# Payload_ESP.net
KiCad netlist of a schematic drawn in Altium Designer
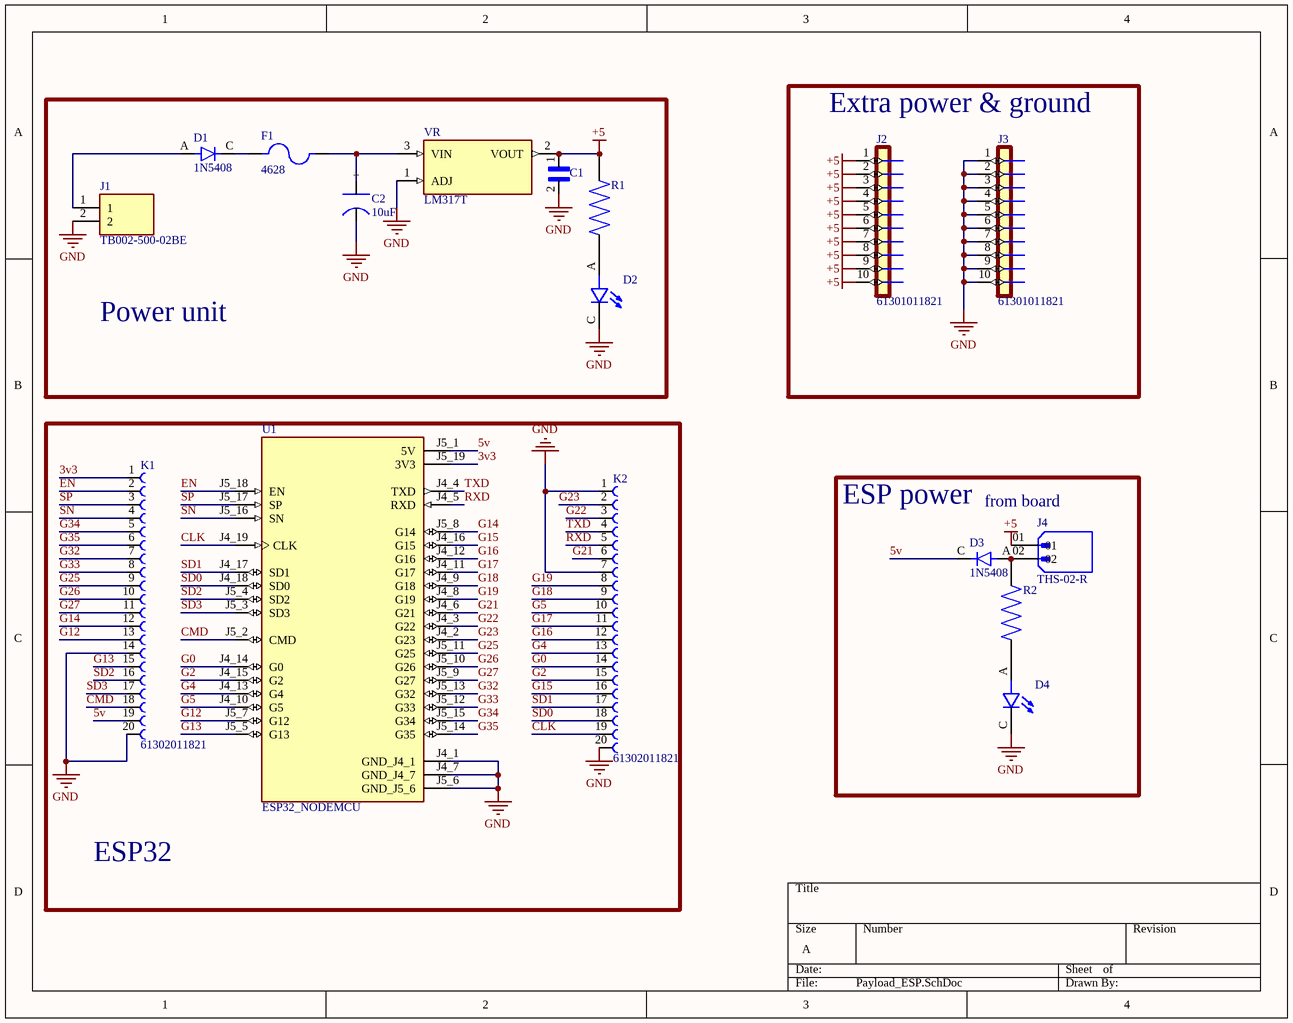
[diagram p0: Payload_ESP.SchDoc]

(export (version "E")
  (design (tool "Eeschema 10.0.6"))
  (components
    (comp (ref "C1")
      (value "FA14X8R1H104KNU06")
      (footprint "CAPRB250W50L450T300H550")
      (description "0.1 ÂµF Â±10% 50V Ceramic Capacitor X8R Radial")
      (fields (field (name "MF") "TDK"))
      (libsource (lib "Martius") (part "FA14X8R1H104KNU06"))
    )
    (comp (ref "C2")
      (value "10uF")
      (footprint "860020672010")
      (libsource (lib "S.M.R") (part "860020672010"))
    )
    (comp (ref "D1")
      (value "1N5408")
      (footprint "DIOAD2006W127L950D530")
      (description "Diode Standard 1000V 3A Through Hole DO-201AD")
      (fields (field (name "MF") "ON"))
      (libsource (lib "Martius") (part "1N5408"))
    )
    (comp (ref "D2")
      (value "151054RS03000")
      (footprint "LED_151054RS03000")
      (description "Red 623nm LED Indication - Discrete 1.9V Radial")
      (fields (field (name "MF") "Wurth Elektronik"))
      (libsource (lib "Martius") (part "151054RS03000"))
    )
    (comp (ref "D3")
      (value "1N5408")
      (footprint "DIOAD2006W127L950D530")
      (description "Diode Standard 1000V 3A Through Hole DO-201AD")
      (fields (field (name "MF") "ON"))
      (libsource (lib "Martius") (part "1N5408"))
    )
    (comp (ref "D4")
      (value "151054RS03000")
      (footprint "LED_151054RS03000")
      (description "Red 623nm LED Indication - Discrete 1.9V Radial")
      (fields (field (name "MF") "Wurth Elektronik"))
      (libsource (lib "Martius") (part "151054RS03000"))
    )
    (comp (ref "F1")
      (value "4628")
      (footprint "FUSE_4628")
      (description "5mm Slim Line Fuse holder")
      (fields (field (name "MF") "Keystone"))
      (libsource (lib "Martius") (part "4628"))
    )
    (comp (ref "J1")
      (value "TB002-500-02BE")
      (footprint "CUI_TB002-500-02BE")
      (description "2~24 Poles, Screw Type, Horizontal, 5.0 Pitch, 22~12 (AWG), Terminal Block Connector")
      (fields (field (name "MF") "CUI Devices"))
      (libsource (lib "Martius") (part "TB002-500-02BE"))
    )
    (comp (ref "J2")
      (value "61301011821")
      (footprint "1X10-PIN")
      (description "10 Position Header Connector 0.100 (2.54mm) Through Hole Gold")
      (fields (field (name "MF") "Wurth Electronics"))
      (libsource (lib "Martius") (part "61301011821"))
    )
    (comp (ref "J3")
      (value "61301011821")
      (footprint "1X10-PIN")
      (description "10 Position Header Connector 0.100 (2.54mm) Through Hole Gold")
      (fields (field (name "MF") "Wurth Electronics"))
      (libsource (lib "Martius") (part "61301011821"))
    )
    (comp (ref "J4")
      (value "THS-02-R")
      (footprint "VALCON_THS-02-R")
      (libsource (lib "Martius") (part "THS-02-R"))
    )
    (comp (ref "K1")
      (value "61302011821")
      (footprint "61302011821")
      (description "20 Position Receptacle Connector 0.100 (2.54mm) Through Hole Gold")
      (fields (field (name "MF") "WÃ¼rth Elektronik"))
      (libsource (lib "Martius") (part "61302011821"))
    )
    (comp (ref "K2")
      (value "61302011821")
      (footprint "61302011821")
      (description "20 Position Receptacle Connector 0.100 (2.54mm) Through Hole Gold")
      (fields (field (name "MF") "WÃ¼rth Elektronik"))
      (libsource (lib "Martius") (part "61302011821"))
    )
    (comp (ref "R1")
      (value "MFR-25FBF52-1K")
      (footprint "RESAD1100W55L680D260")
      (description "1.07 kOhms Â±1% 0.25W, 1/4W Through Hole Resistor Axial - Metal Film")
      (fields (field (name "MF") "Yageo"))
      (libsource (lib "Martius") (part "MFR-25FBF52-1K"))
    )
    (comp (ref "R2")
      (value "MFR-25FBF52-1K")
      (footprint "RESAD1100W55L680D260")
      (description "1.07 kOhms Â±1% 0.25W, 1/4W Through Hole Resistor Axial - Metal Film")
      (fields (field (name "MF") "Yageo"))
      (libsource (lib "Martius") (part "MFR-25FBF52-1K"))
    )
    (comp (ref "U1")
      (value "ESP32_NODEMCU")
      (footprint "MODULE_ESP32_NODEMCU")
      (fields (field (name "MF") "Espressif Systems") (field (name "MP") "ESP32 NODEMCU"))
      (libsource (lib "Martius") (part "ESP32_NODEMCU"))
    )
    (comp (ref "VR")
      (value "LM317T")
      (footprint "TO254P1054X470X1955-3")
      (description "Linear Voltage Regulator IC 1 Output 1.5A TO-220-3")
      (fields (field (name "MF") "Texas Instruments"))
      (libsource (lib "Martius") (part "LM317T"))
    )
  )
  (nets
    (net (code "1") (name "+5") (class "Default")
      (node (ref "C1") (pin "1") (pinfunction "1_1") (pintype "passive"))
      (node (ref "J2") (pin "1") (pinfunction "1_1") (pintype "bidirectional"))
      (node (ref "J2") (pin "10") (pinfunction "10_10") (pintype "bidirectional"))
      (node (ref "J2") (pin "2") (pinfunction "2_2") (pintype "bidirectional"))
      (node (ref "J2") (pin "3") (pinfunction "3_3") (pintype "bidirectional"))
      (node (ref "J2") (pin "4") (pinfunction "4_4") (pintype "bidirectional"))
      (node (ref "J2") (pin "5") (pinfunction "5_5") (pintype "bidirectional"))
      (node (ref "J2") (pin "6") (pinfunction "6_6") (pintype "bidirectional"))
      (node (ref "J2") (pin "7") (pinfunction "7_7") (pintype "bidirectional"))
      (node (ref "J2") (pin "8") (pinfunction "8_8") (pintype "bidirectional"))
      (node (ref "J2") (pin "9") (pinfunction "9_9") (pintype "bidirectional"))
      (node (ref "J4") (pin "01") (pinfunction "01_01") (pintype "passive"))
      (node (ref "R1") (pin "2") (pinfunction "2_2") (pintype "passive"))
      (node (ref "VR") (pin "2") (pinfunction "VOUT_2") (pintype "output"))
    )
    (net (code "2") (name "/3v3") (class "Default")
      (node (ref "K1") (pin "1") (pinfunction "1_1") (pintype "passive"))
      (node (ref "U1") (pin "J5_19") (pinfunction "3V3_J5_19") (pintype "power_in"))
    )
    (net (code "3") (name "/5v") (class "Default")
      (node (ref "D3") (pin "C") (pinfunction "C_C") (pintype "passive"))
      (node (ref "K1") (pin "19") (pinfunction "19_19") (pintype "passive"))
      (node (ref "U1") (pin "J5_1") (pinfunction "5V_J5_1") (pintype "power_in"))
    )
    (net (code "5") (name "/CLK") (class "Default")
      (node (ref "K2") (pin "19") (pinfunction "19_19") (pintype "passive"))
      (node (ref "U1") (pin "J4_19") (pinfunction "CLK_J4_19") (pintype "input"))
    )
    (net (code "6") (name "/CMD") (class "Default")
      (node (ref "K1") (pin "18") (pinfunction "18_18") (pintype "passive"))
      (node (ref "U1") (pin "J5_2") (pinfunction "CMD_J5_2") (pintype "bidirectional"))
    )
    (net (code "7") (name "/EN") (class "Default")
      (node (ref "K1") (pin "2") (pinfunction "2_2") (pintype "passive"))
      (node (ref "U1") (pin "J5_18") (pinfunction "EN_J5_18") (pintype "input"))
    )
    (net (code "8") (name "/G0") (class "Default")
      (node (ref "K2") (pin "14") (pinfunction "14_14") (pintype "passive"))
      (node (ref "U1") (pin "J4_14") (pinfunction "G0_J4_14") (pintype "bidirectional"))
    )
    (net (code "9") (name "/G2") (class "Default")
      (node (ref "K2") (pin "15") (pinfunction "15_15") (pintype "passive"))
      (node (ref "U1") (pin "J4_15") (pinfunction "G2_J4_15") (pintype "bidirectional"))
    )
    (net (code "10") (name "/G4") (class "Default")
      (node (ref "K2") (pin "13") (pinfunction "13_13") (pintype "passive"))
      (node (ref "U1") (pin "J4_13") (pinfunction "G4_J4_13") (pintype "bidirectional"))
    )
    (net (code "11") (name "/G5") (class "Default")
      (node (ref "K2") (pin "10") (pinfunction "10_10") (pintype "passive"))
      (node (ref "U1") (pin "J4_10") (pinfunction "G5_J4_10") (pintype "bidirectional"))
    )
    (net (code "12") (name "/G12") (class "Default")
      (node (ref "K1") (pin "13") (pinfunction "13_13") (pintype "passive"))
      (node (ref "U1") (pin "J5_7") (pinfunction "G12_J5_7") (pintype "bidirectional"))
    )
    (net (code "13") (name "/G13") (class "Default")
      (node (ref "K1") (pin "15") (pinfunction "15_15") (pintype "passive"))
      (node (ref "U1") (pin "J5_5") (pinfunction "G13_J5_5") (pintype "bidirectional"))
    )
    (net (code "14") (name "/G14") (class "Default")
      (node (ref "K1") (pin "12") (pinfunction "12_12") (pintype "passive"))
      (node (ref "U1") (pin "J5_8") (pinfunction "G14_J5_8") (pintype "bidirectional"))
    )
    (net (code "15") (name "/G15") (class "Default")
      (node (ref "K2") (pin "16") (pinfunction "16_16") (pintype "passive"))
      (node (ref "U1") (pin "J4_16") (pinfunction "G15_J4_16") (pintype "bidirectional"))
    )
    (net (code "16") (name "/G16") (class "Default")
      (node (ref "K2") (pin "12") (pinfunction "12_12") (pintype "passive"))
      (node (ref "U1") (pin "J4_12") (pinfunction "G16_J4_12") (pintype "bidirectional"))
    )
    (net (code "17") (name "/G17") (class "Default")
      (node (ref "K2") (pin "11") (pinfunction "11_11") (pintype "passive"))
      (node (ref "U1") (pin "J4_11") (pinfunction "G17_J4_11") (pintype "bidirectional"))
    )
    (net (code "18") (name "/G18") (class "Default")
      (node (ref "K2") (pin "9") (pinfunction "9_9") (pintype "passive"))
      (node (ref "U1") (pin "J4_9") (pinfunction "G18_J4_9") (pintype "bidirectional"))
    )
    (net (code "19") (name "/G19") (class "Default")
      (node (ref "K2") (pin "8") (pinfunction "8_8") (pintype "passive"))
      (node (ref "U1") (pin "J4_8") (pinfunction "G19_J4_8") (pintype "bidirectional"))
    )
    (net (code "20") (name "/G21") (class "Default")
      (node (ref "K2") (pin "6") (pinfunction "6_6") (pintype "passive"))
      (node (ref "U1") (pin "J4_6") (pinfunction "G21_J4_6") (pintype "bidirectional"))
    )
    (net (code "21") (name "/G22") (class "Default")
      (node (ref "K2") (pin "3") (pinfunction "3_3") (pintype "passive"))
      (node (ref "U1") (pin "J4_3") (pinfunction "G22_J4_3") (pintype "bidirectional"))
    )
    (net (code "22") (name "/G23") (class "Default")
      (node (ref "K2") (pin "2") (pinfunction "2_2") (pintype "passive"))
      (node (ref "U1") (pin "J4_2") (pinfunction "G23_J4_2") (pintype "bidirectional"))
    )
    (net (code "23") (name "/G25") (class "Default")
      (node (ref "K1") (pin "9") (pinfunction "9_9") (pintype "passive"))
      (node (ref "U1") (pin "J5_11") (pinfunction "G25_J5_11") (pintype "bidirectional"))
    )
    (net (code "24") (name "/G26") (class "Default")
      (node (ref "K1") (pin "10") (pinfunction "10_10") (pintype "passive"))
      (node (ref "U1") (pin "J5_10") (pinfunction "G26_J5_10") (pintype "bidirectional"))
    )
    (net (code "25") (name "/G27") (class "Default")
      (node (ref "K1") (pin "11") (pinfunction "11_11") (pintype "passive"))
      (node (ref "U1") (pin "J5_9") (pinfunction "G27_J5_9") (pintype "bidirectional"))
    )
    (net (code "26") (name "/G32") (class "Default")
      (node (ref "K1") (pin "7") (pinfunction "7_7") (pintype "passive"))
      (node (ref "U1") (pin "J5_13") (pinfunction "G32_J5_13") (pintype "bidirectional"))
    )
    (net (code "27") (name "/G33") (class "Default")
      (node (ref "K1") (pin "8") (pinfunction "8_8") (pintype "passive"))
      (node (ref "U1") (pin "J5_12") (pinfunction "G33_J5_12") (pintype "bidirectional"))
    )
    (net (code "28") (name "/G34") (class "Default")
      (node (ref "K1") (pin "5") (pinfunction "5_5") (pintype "passive"))
      (node (ref "U1") (pin "J5_15") (pinfunction "G34_J5_15") (pintype "bidirectional"))
    )
    (net (code "29") (name "/G35") (class "Default")
      (node (ref "K1") (pin "6") (pinfunction "6_6") (pintype "passive"))
      (node (ref "U1") (pin "J5_14") (pinfunction "G35_J5_14") (pintype "bidirectional"))
    )
    (net (code "30") (name "/RXD") (class "Default")
      (node (ref "K2") (pin "5") (pinfunction "5_5") (pintype "passive"))
      (node (ref "U1") (pin "J4_5") (pinfunction "RXD_J4_5") (pintype "input"))
    )
    (net (code "31") (name "/SD0") (class "Default")
      (node (ref "K2") (pin "18") (pinfunction "18_18") (pintype "passive"))
      (node (ref "U1") (pin "J4_18") (pinfunction "SD0_J4_18") (pintype "bidirectional"))
    )
    (net (code "32") (name "/SD1") (class "Default")
      (node (ref "K2") (pin "17") (pinfunction "17_17") (pintype "passive"))
      (node (ref "U1") (pin "J4_17") (pinfunction "SD1_J4_17") (pintype "bidirectional"))
    )
    (net (code "33") (name "/SD2") (class "Default")
      (node (ref "K1") (pin "16") (pinfunction "16_16") (pintype "passive"))
      (node (ref "U1") (pin "J5_4") (pinfunction "SD2_J5_4") (pintype "bidirectional"))
    )
    (net (code "34") (name "/SD3") (class "Default")
      (node (ref "K1") (pin "17") (pinfunction "17_17") (pintype "passive"))
      (node (ref "U1") (pin "J5_3") (pinfunction "SD3_J5_3") (pintype "bidirectional"))
    )
    (net (code "35") (name "/SN") (class "Default")
      (node (ref "K1") (pin "4") (pinfunction "4_4") (pintype "passive"))
      (node (ref "U1") (pin "J5_16") (pinfunction "SN_J5_16") (pintype "input"))
    )
    (net (code "36") (name "/SP") (class "Default")
      (node (ref "K1") (pin "3") (pinfunction "3_3") (pintype "passive"))
      (node (ref "U1") (pin "J5_17") (pinfunction "SP_J5_17") (pintype "input"))
    )
    (net (code "37") (name "/TXD") (class "Default")
      (node (ref "K2") (pin "4") (pinfunction "4_4") (pintype "passive"))
      (node (ref "U1") (pin "J4_4") (pinfunction "TXD_J4_4") (pintype "output"))
    )
    (net (code "38") (name "GND") (class "Default")
      (node (ref "C1") (pin "2") (pinfunction "2_2") (pintype "passive"))
      (node (ref "C2") (pin "2") (pinfunction "-_2") (pintype "passive"))
      (node (ref "D2") (pin "C") (pinfunction "C_C") (pintype "passive"))
      (node (ref "D4") (pin "C") (pinfunction "C_C") (pintype "passive"))
      (node (ref "J1") (pin "2") (pinfunction "2_2") (pintype "passive"))
      (node (ref "J3") (pin "1") (pinfunction "1_1") (pintype "bidirectional"))
      (node (ref "J3") (pin "10") (pinfunction "10_10") (pintype "bidirectional"))
      (node (ref "J3") (pin "2") (pinfunction "2_2") (pintype "bidirectional"))
      (node (ref "J3") (pin "3") (pinfunction "3_3") (pintype "bidirectional"))
      (node (ref "J3") (pin "4") (pinfunction "4_4") (pintype "bidirectional"))
      (node (ref "J3") (pin "5") (pinfunction "5_5") (pintype "bidirectional"))
      (node (ref "J3") (pin "6") (pinfunction "6_6") (pintype "bidirectional"))
      (node (ref "J3") (pin "7") (pinfunction "7_7") (pintype "bidirectional"))
      (node (ref "J3") (pin "8") (pinfunction "8_8") (pintype "bidirectional"))
      (node (ref "J3") (pin "9") (pinfunction "9_9") (pintype "bidirectional"))
      (node (ref "K1") (pin "14") (pinfunction "14_14") (pintype "passive"))
      (node (ref "K1") (pin "20") (pinfunction "20_20") (pintype "passive"))
      (node (ref "K2") (pin "1") (pinfunction "1_1") (pintype "passive"))
      (node (ref "K2") (pin "20") (pinfunction "20_20") (pintype "passive"))
      (node (ref "K2") (pin "7") (pinfunction "7_7") (pintype "passive"))
      (node (ref "U1") (pin "J4_1") (pinfunction "GND_J4_1_J4_1") (pintype "power_in"))
      (node (ref "U1") (pin "J4_7") (pinfunction "GND_J4_7_J4_7") (pintype "power_in"))
      (node (ref "U1") (pin "J5_6") (pinfunction "GND_J5_6_J5_6") (pintype "power_in"))
      (node (ref "VR") (pin "1") (pinfunction "ADJ_1") (pintype "input"))
    )
    (net (code "39") (name "Net-(C2-+)") (class "Default")
      (node (ref "C2") (pin "1") (pinfunction "+_1") (pintype "passive"))
      (node (ref "F1") (pin "2") (pinfunction "2_2") (pintype "passive"))
      (node (ref "VR") (pin "3") (pinfunction "VIN_3") (pintype "input"))
    )
    (net (code "40") (name "Net-(D1-PadA)") (class "Default")
      (node (ref "D1") (pin "A") (pinfunction "A_A") (pintype "passive"))
      (node (ref "J1") (pin "1") (pinfunction "1_1") (pintype "passive"))
    )
    (net (code "41") (name "Net-(D1-PadC)") (class "Default")
      (node (ref "D1") (pin "C") (pinfunction "C_C") (pintype "passive"))
      (node (ref "F1") (pin "1") (pinfunction "1_1") (pintype "passive"))
    )
    (net (code "42") (name "Net-(D2-PadA)") (class "Default")
      (node (ref "D2") (pin "A") (pinfunction "A_A") (pintype "passive"))
      (node (ref "R1") (pin "1") (pinfunction "1_1") (pintype "passive"))
    )
    (net (code "43") (name "Net-(D3-PadA)") (class "Default")
      (node (ref "D3") (pin "A") (pinfunction "A_A") (pintype "passive"))
      (node (ref "J4") (pin "02") (pinfunction "02_02") (pintype "passive"))
      (node (ref "R2") (pin "2") (pinfunction "2_2") (pintype "passive"))
    )
    (net (code "44") (name "Net-(D4-PadA)") (class "Default")
      (node (ref "D4") (pin "A") (pinfunction "A_A") (pintype "passive"))
      (node (ref "R2") (pin "1") (pinfunction "1_1") (pintype "passive"))
    )
  )
)
